# 3_VW_Sensor.net
KiCad netlist of a schematic drawn in Altium Designer
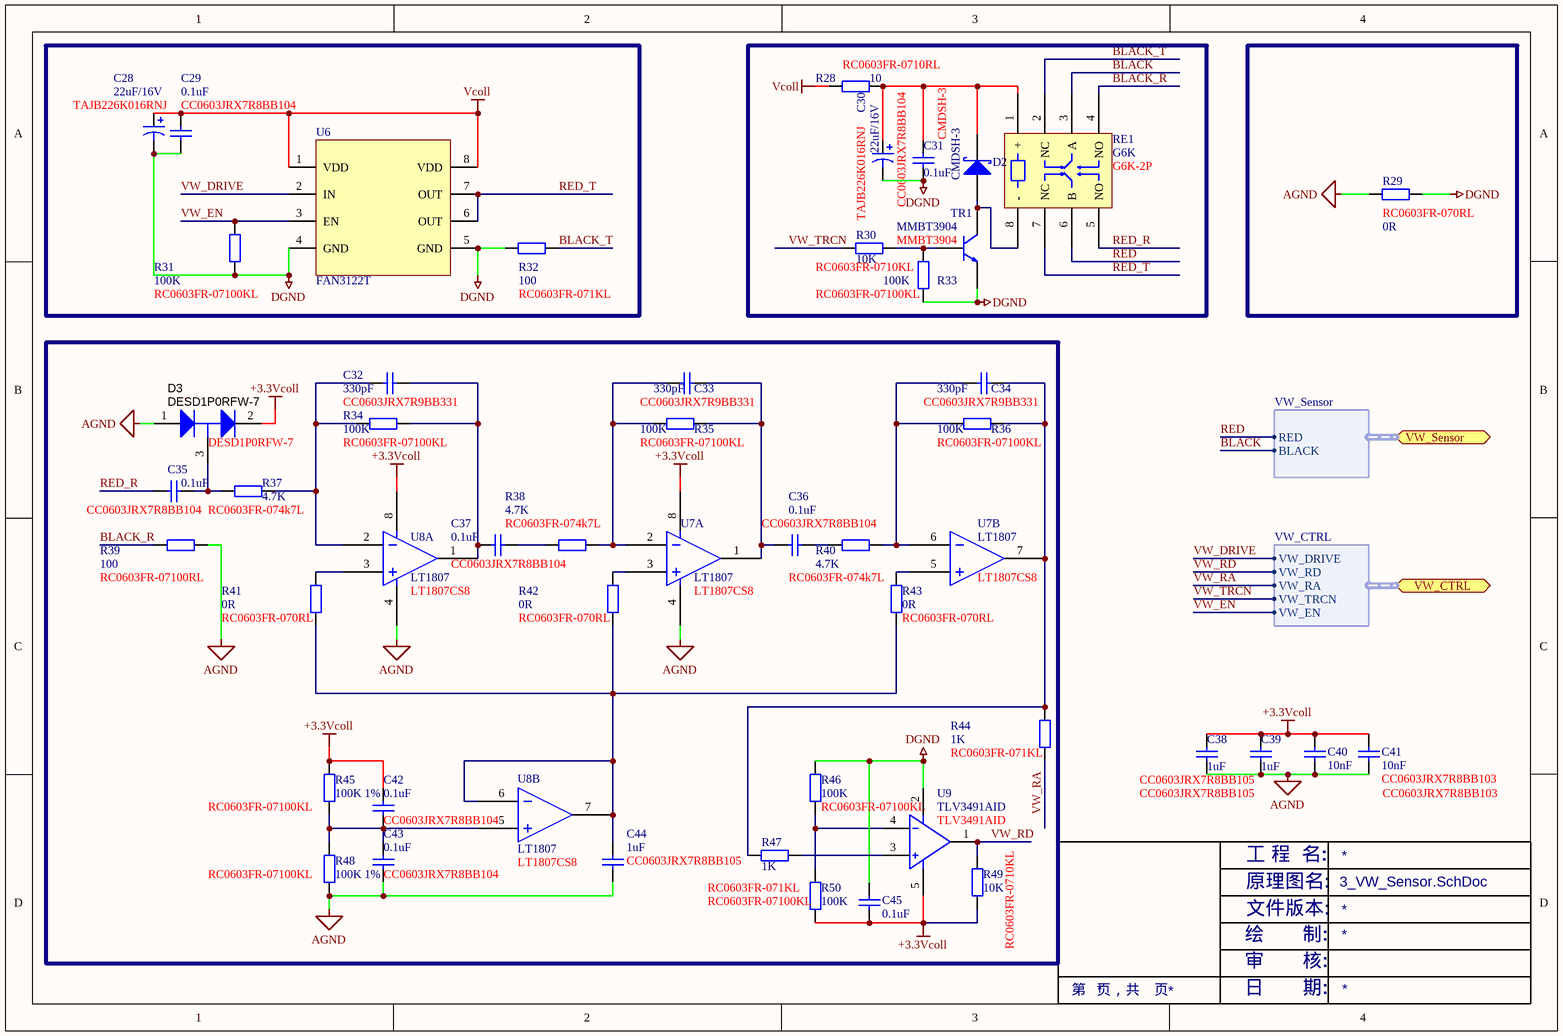
[diagram p0: 3_VW_Sensor.SchDoc]

(export (version "E")
  (design (tool "Eeschema 10.0.6"))
  (components
    (comp (ref "C28")
      (value "22uF/16V")
      (footprint "CB3528")
      (description "Polarized Capacitor (Radial)")
      (fields (field (name "PART NO.") "TAJB226K016RNJ"))
      (libsource (lib "Miscellaneous Devices") (part "Cap Pol1"))
    )
    (comp (ref "C29")
      (value "0.1uF")
      (footprint "CC0603")
      (description "Capacitor")
      (fields (field (name "TYPE NO.") "CC0603JRX7R8BB104"))
      (libsource (lib "Miscellaneous Devices") (part "Cap"))
    )
    (comp (ref "C30")
      (value "22uF/16V")
      (footprint "CB3528")
      (description "Polarized Capacitor (Radial)")
      (fields (field (name "PART NO.") "TAJB226K016RNJ"))
      (libsource (lib "Miscellaneous Devices") (part "Cap Pol1"))
    )
    (comp (ref "C31")
      (value "0.1uF")
      (footprint "CC0603")
      (description "Capacitor")
      (fields (field (name "TYPE NO.") "CC0603JRX7R8BB104"))
      (libsource (lib "Miscellaneous Devices") (part "Cap"))
    )
    (comp (ref "C32")
      (value "330pF")
      (footprint "CC0603")
      (description "Capacitor")
      (fields (field (name "TYPE NO.") "CC0603JRX7R9BB331"))
      (libsource (lib "Miscellaneous Devices") (part "Cap"))
    )
    (comp (ref "C33")
      (value "330pF")
      (footprint "CC0603")
      (description "Capacitor")
      (fields (field (name "TYPE NO.") "CC0603JRX7R9BB331"))
      (libsource (lib "Miscellaneous Devices") (part "Cap"))
    )
    (comp (ref "C34")
      (value "330pF")
      (footprint "CC0603")
      (description "Capacitor")
      (fields (field (name "TYPE NO.") "CC0603JRX7R9BB331"))
      (libsource (lib "Miscellaneous Devices") (part "Cap"))
    )
    (comp (ref "C35")
      (value "0.1uF")
      (footprint "CC0603")
      (description "Capacitor")
      (fields (field (name "TYPE NO.") "CC0603JRX7R8BB104"))
      (libsource (lib "Miscellaneous Devices") (part "Cap"))
    )
    (comp (ref "C36")
      (value "0.1uF")
      (footprint "CC0603")
      (description "Capacitor")
      (fields (field (name "TYPE NO.") "CC0603JRX7R8BB104"))
      (libsource (lib "Miscellaneous Devices") (part "Cap"))
    )
    (comp (ref "C37")
      (value "0.1uF")
      (footprint "CC0603")
      (description "Capacitor")
      (fields (field (name "TYPE NO.") "CC0603JRX7R8BB104"))
      (libsource (lib "Miscellaneous Devices") (part "Cap"))
    )
    (comp (ref "C38")
      (value "1uF")
      (footprint "CC0603")
      (description "Capacitor")
      (fields (field (name "TYPE NO.") "CC0603JRX7R8BB105"))
      (libsource (lib "Miscellaneous Devices") (part "Cap"))
    )
    (comp (ref "C39")
      (value "1uF")
      (footprint "CC0603")
      (description "Capacitor")
      (fields (field (name "TYPE NO.") "CC0603JRX7R8BB105"))
      (libsource (lib "Miscellaneous Devices") (part "Cap"))
    )
    (comp (ref "C40")
      (value "10nF")
      (footprint "CC0603")
      (description "Capacitor")
      (fields (field (name "TYPE NO.") "CC0603JRX7R8BB103"))
      (libsource (lib "Miscellaneous Devices") (part "Cap"))
    )
    (comp (ref "C41")
      (value "10nF")
      (footprint "CC0603")
      (description "Capacitor")
      (fields (field (name "TYPE NO.") "CC0603JRX7R8BB103"))
      (libsource (lib "Miscellaneous Devices") (part "Cap"))
    )
    (comp (ref "C42")
      (value "0.1uF")
      (footprint "CC0603")
      (description "Capacitor")
      (fields (field (name "TYPE NO.") "CC0603JRX7R8BB104"))
      (libsource (lib "Miscellaneous Devices") (part "Cap"))
    )
    (comp (ref "C43")
      (value "0.1uF")
      (footprint "CC0603")
      (description "Capacitor")
      (fields (field (name "TYPE NO.") "CC0603JRX7R8BB104"))
      (libsource (lib "Miscellaneous Devices") (part "Cap"))
    )
    (comp (ref "C44")
      (value "1uF")
      (footprint "CC0603")
      (description "Capacitor")
      (fields (field (name "TYPE NO.") "CC0603JRX7R8BB105"))
      (libsource (lib "Miscellaneous Devices") (part "Cap"))
    )
    (comp (ref "C45")
      (value "0.1uF")
      (footprint "CC0603")
      (description "Capacitor")
      (fields (field (name "PUBLISHER") "Altium Limited"))
      (libsource (lib "Miscellaneous Devices") (part "Cap"))
    )
    (comp (ref "D2")
      (value "CMDSH-3")
      (footprint "SOD323")
      (description "Schottky Diode")
      (fields (field (name "TYPE NO.") "CMDSH-3"))
      (libsource (lib "Miscellaneous Devices") (part "D Schottky"))
    )
    (comp (ref "D3")
      (value "DESD1P0RFW-7")
      (footprint "SOT-323")
      (description "TVS DIODE,70VVVM,8VC,SOT-323")
      (fields (field (name "TYPE NO.") "DESD1P0RFW-7"))
      (libsource (lib "Diode") (part "BAV99WT1G"))
    )
    (comp (ref "R28")
      (value "10")
      (footprint "CC0603")
      (description "Resistor")
      (fields (field (name "TYPE NO.") "RC0603FR-0710RL"))
      (libsource (lib "") (part "Res2_3"))
    )
    (comp (ref "R29")
      (value "0R")
      (footprint "CC0603")
      (description "Resistor")
      (fields (field (name "TYPE NO.") "RC0603FR-070RL"))
      (libsource (lib "") (part "Res2_2"))
    )
    (comp (ref "R30")
      (value "10K")
      (footprint "CC0603")
      (description "Resistor")
      (fields (field (name "TYPE NO.") "RC0603FR-0710KL"))
      (libsource (lib "") (part "Res2_3"))
    )
    (comp (ref "R31")
      (value "100K")
      (footprint "CC0603")
      (description "Resistor")
      (fields (field (name "TYPE NO.") "RC0603FR-07100KL"))
      (libsource (lib "") (part "Res2_1"))
    )
    (comp (ref "R32")
      (value "100")
      (footprint "CC0603")
      (description "Resistor")
      (fields (field (name "TYPE NO.") "RC0603FR-071KL"))
      (libsource (lib "Miscellaneous Devices") (part "Res2"))
    )
    (comp (ref "R33")
      (value "100K")
      (footprint "CC0603")
      (description "Resistor")
      (fields (field (name "TYPE NO.") "RC0603FR-07100KL"))
      (libsource (lib "") (part "Res2_2"))
    )
    (comp (ref "R34")
      (value "100K")
      (footprint "CC0603")
      (description "Resistor")
      (fields (field (name "TYPE NO.") "RC0603FR-07100KL"))
      (libsource (lib "Miscellaneous Devices") (part "Res2"))
    )
    (comp (ref "R35")
      (value "100K")
      (footprint "CC0603")
      (description "Resistor")
      (fields (field (name "TYPE NO.") "RC0603FR-07100KL"))
      (libsource (lib "Miscellaneous Devices") (part "Res2"))
    )
    (comp (ref "R36")
      (value "100K")
      (footprint "CC0603")
      (description "Resistor")
      (fields (field (name "TYPE NO.") "RC0603FR-07100KL"))
      (libsource (lib "Miscellaneous Devices") (part "Res2"))
    )
    (comp (ref "R37")
      (value "4.7K")
      (footprint "CC0603")
      (description "Resistor")
      (fields (field (name "TYPE NO.") "RC0603FR-074k7L"))
      (libsource (lib "Miscellaneous Devices") (part "Res2"))
    )
    (comp (ref "R38")
      (value "4.7K")
      (footprint "CC0603")
      (description "Resistor")
      (fields (field (name "TYPE NO.") "RC0603FR-074k7L"))
      (libsource (lib "Miscellaneous Devices") (part "Res2"))
    )
    (comp (ref "R39")
      (value "100")
      (footprint "CC0603")
      (description "Resistor")
      (fields (field (name "TYPE NO.") "RC0603FR-07100RL"))
      (libsource (lib "") (part "Res2_2"))
    )
    (comp (ref "R40")
      (value "4.7K")
      (footprint "CC0603")
      (description "Resistor")
      (fields (field (name "TYPE NO.") "RC0603FR-074k7L"))
      (libsource (lib "Miscellaneous Devices") (part "Res2"))
    )
    (comp (ref "R41")
      (value "0R")
      (footprint "CC0603")
      (description "Resistor")
      (fields (field (name "TYPE NO.") "RC0603FR-070RL"))
      (libsource (lib "") (part "Res2_1"))
    )
    (comp (ref "R42")
      (value "0R")
      (footprint "CC0603")
      (description "Resistor")
      (fields (field (name "TYPE NO.") "RC0603FR-070RL"))
      (libsource (lib "") (part "Res2_1"))
    )
    (comp (ref "R43")
      (value "0R")
      (footprint "CC0603")
      (description "Resistor")
      (fields (field (name "TYPE NO.") "RC0603FR-070RL"))
      (libsource (lib "") (part "Res2_1"))
    )
    (comp (ref "R44")
      (value "1K")
      (footprint "CC0603")
      (description "Resistor")
      (fields (field (name "TYPE NO.") "RC0603FR-071KL"))
      (libsource (lib "") (part "Res2_1"))
    )
    (comp (ref "R45")
      (value "100K 1%")
      (footprint "CC0603")
      (description "Resistor")
      (fields (field (name "TYPE NO.") "RC0603FR-07100KL"))
      (libsource (lib "") (part "Res2_1"))
    )
    (comp (ref "R46")
      (value "100K")
      (footprint "CC0603")
      (description "Resistor")
      (fields (field (name "TYPE NO.") "RC0603FR-07100KL"))
      (libsource (lib "") (part "Res2_3"))
    )
    (comp (ref "R47")
      (value "1K")
      (footprint "CC0603")
      (description "Resistor")
      (fields (field (name "TYPE NO.") "RC0603FR-071KL"))
      (libsource (lib "Miscellaneous Devices") (part "Res2"))
    )
    (comp (ref "R48")
      (value "100K 1%")
      (footprint "CC0603")
      (description "Resistor")
      (fields (field (name "TYPE NO.") "RC0603FR-07100KL"))
      (libsource (lib "") (part "Res2_1"))
    )
    (comp (ref "R49")
      (value "10K")
      (footprint "CC0603")
      (description "Resistor")
      (fields (field (name "TYPE NO.") "RC0603FR-0710KL"))
      (libsource (lib "") (part "Res2_3"))
    )
    (comp (ref "R50")
      (value "100K")
      (footprint "CC0603")
      (description "Resistor")
      (fields (field (name "TYPE NO.") "RC0603FR-07100KL"))
      (libsource (lib "") (part "Res2_3"))
    )
    (comp (ref "RE1")
      (value "G6K")
      (footprint "G6K")
      (fields (field (name "TYPE NO.") "G6K-2P"))
      (libsource (lib "woylib2015") (part "G6K"))
    )
    (comp (ref "TR1")
      (value "MMBT3904")
      (footprint "SOT-23W")
      (fields (field (name "TYPE NO.") "MMBT3904"))
      (libsource (lib "Discrete") (part "NPN"))
    )
    (comp (ref "U6") (value "FAN3122T") (footprint "SO-8") (libsource (lib "IC") (part "FAN3122")))
    (comp (ref "U7")
      (value "LT1807")
      (footprint "SO-8")
      (fields (field (name "TYPE NO.") "LT1807CS8"))
      (libsource (lib "woylib2015") (part "LM833N"))
    )
    (comp (ref "U8")
      (value "LT1807")
      (footprint "SO-8")
      (fields (field (name "TYPE NO.") "LT1807CS8"))
      (libsource (lib "woylib2015") (part "LM833N"))
    )
    (comp (ref "U9")
      (value "TLV3491AID")
      (footprint "SOT-23-5")
      (fields (field (name "TYPE NO.") "TLV3491AID"))
      (libsource (lib "woylib2015") (part "TLV3491AID"))
    )
  )
  (nets
    (net (code "3") (name "+3.3Vcoll") (class "Default")
      (node (ref "C38") (pin "2") (pinfunction "2_2") (pintype "passive"))
      (node (ref "C39") (pin "2") (pinfunction "2_2") (pintype "passive"))
      (node (ref "C40") (pin "1") (pinfunction "1_1") (pintype "passive"))
      (node (ref "C41") (pin "1") (pinfunction "1_1") (pintype "passive"))
      (node (ref "C42") (pin "1") (pinfunction "1_1") (pintype "passive"))
      (node (ref "C45") (pin "2") (pinfunction "2_2") (pintype "passive"))
      (node (ref "D3") (pin "2") (pinfunction "K_2") (pintype "passive"))
      (node (ref "R45") (pin "1") (pinfunction "1_1") (pintype "passive"))
      (node (ref "R49") (pin "1") (pinfunction "1_1") (pintype "passive"))
      (node (ref "R50") (pin "1") (pinfunction "1_1") (pintype "passive"))
      (node (ref "U7") (pin "8") (pintype "passive"))
      (node (ref "U8") (pin "8") (pintype "passive"))
      (node (ref "U9") (pin "5") (pinfunction "+VS_5") (pintype "passive"))
    )
    (net (code "4") (name "/BLACK") (class "Default")
      (node (ref "RE1") (pin "3") (pinfunction "A_3") (pintype "passive"))
    )
    (net (code "5") (name "/BLACK_R") (class "Default")
      (node (ref "R39") (pin "1") (pinfunction "1_1") (pintype "passive"))
      (node (ref "RE1") (pin "4") (pinfunction "NO_4") (pintype "passive"))
    )
    (net (code "6") (name "/BLACK_T") (class "Default")
      (node (ref "R32") (pin "1") (pinfunction "1_1") (pintype "passive"))
      (node (ref "RE1") (pin "2") (pinfunction "NC_2") (pintype "passive"))
    )
    (net (code "7") (name "/RED") (class "Default")
      (node (ref "RE1") (pin "6") (pinfunction "B_6") (pintype "passive"))
    )
    (net (code "8") (name "/RED_R") (class "Default")
      (node (ref "C35") (pin "2") (pinfunction "2_2") (pintype "passive"))
      (node (ref "RE1") (pin "5") (pinfunction "NO_5") (pintype "passive"))
    )
    (net (code "9") (name "/RED_T") (class "Default")
      (node (ref "RE1") (pin "7") (pinfunction "NC_7") (pintype "passive"))
      (node (ref "U6") (pin "6") (pinfunction "OUT_6") (pintype "passive"))
      (node (ref "U6") (pin "7") (pinfunction "OUT_7") (pintype "passive"))
    )
    (net (code "10") (name "/VW_DRIVE") (class "Default")
      (node (ref "U6") (pin "2") (pinfunction "IN_2") (pintype "passive"))
    )
    (net (code "11") (name "/VW_EN") (class "Default")
      (node (ref "R31") (pin "1") (pinfunction "1_1") (pintype "passive"))
      (node (ref "U6") (pin "3") (pinfunction "EN_3") (pintype "passive"))
    )
    (net (code "12") (name "/VW_RA") (class "Default")
      (node (ref "R44") (pin "2") (pinfunction "2_2") (pintype "passive"))
    )
    (net (code "13") (name "/VW_RD") (class "Default")
      (node (ref "R49") (pin "2") (pinfunction "2_2") (pintype "passive"))
      (node (ref "U9") (pin "1") (pinfunction "OUT_1") (pintype "passive"))
    )
    (net (code "14") (name "/VW_TRCN") (class "Default")
      (node (ref "R30") (pin "1") (pinfunction "1_1") (pintype "passive"))
    )
    (net (code "17") (name "AGND") (class "Default")
      (node (ref "C38") (pin "1") (pinfunction "1_1") (pintype "passive"))
      (node (ref "C39") (pin "1") (pinfunction "1_1") (pintype "passive"))
      (node (ref "C40") (pin "2") (pinfunction "2_2") (pintype "passive"))
      (node (ref "C41") (pin "2") (pinfunction "2_2") (pintype "passive"))
      (node (ref "C43") (pin "2") (pinfunction "2_2") (pintype "passive"))
      (node (ref "C44") (pin "1") (pinfunction "1_1") (pintype "passive"))
      (node (ref "D3") (pin "1") (pinfunction "A_1") (pintype "passive"))
      (node (ref "R29") (pin "1") (pinfunction "1_1") (pintype "passive"))
      (node (ref "R39") (pin "2") (pinfunction "2_2") (pintype "passive"))
      (node (ref "R48") (pin "2") (pinfunction "2_2") (pintype "passive"))
      (node (ref "U7") (pin "4") (pintype "passive"))
      (node (ref "U8") (pin "4") (pintype "passive"))
    )
    (net (code "18") (name "DGND") (class "Default")
      (node (ref "C28") (pin "2") (pinfunction "2_2") (pintype "passive"))
      (node (ref "C29") (pin "1") (pinfunction "1_1") (pintype "passive"))
      (node (ref "C30") (pin "2") (pinfunction "2_2") (pintype "passive"))
      (node (ref "C31") (pin "2") (pinfunction "2_2") (pintype "passive"))
      (node (ref "C45") (pin "1") (pinfunction "1_1") (pintype "passive"))
      (node (ref "R29") (pin "2") (pinfunction "2_2") (pintype "passive"))
      (node (ref "R31") (pin "2") (pinfunction "2_2") (pintype "passive"))
      (node (ref "R32") (pin "2") (pinfunction "2_2") (pintype "passive"))
      (node (ref "R33") (pin "1") (pinfunction "1_1") (pintype "passive"))
      (node (ref "R46") (pin "2") (pinfunction "2_2") (pintype "passive"))
      (node (ref "TR1") (pin "2") (pinfunction "2_2") (pintype "passive"))
      (node (ref "U6") (pin "4") (pinfunction "GND_4") (pintype "passive"))
      (node (ref "U6") (pin "5") (pinfunction "GND_5") (pintype "passive"))
      (node (ref "U9") (pin "2") (pinfunction "-VS_2") (pintype "passive"))
    )
    (net (code "19") (name "Net-(C32-Pad1)") (class "Default")
      (node (ref "C32") (pin "1") (pinfunction "1_1") (pintype "passive"))
      (node (ref "C37") (pin "2") (pinfunction "2_2") (pintype "passive"))
      (node (ref "R34") (pin "1") (pinfunction "1_1") (pintype "passive"))
      (node (ref "U8") (pin "1") (pintype "passive"))
    )
    (net (code "20") (name "Net-(C32-Pad2)") (class "Default")
      (node (ref "C32") (pin "2") (pinfunction "2_2") (pintype "passive"))
      (node (ref "R34") (pin "2") (pinfunction "2_2") (pintype "passive"))
      (node (ref "R37") (pin "1") (pinfunction "1_1") (pintype "passive"))
      (node (ref "U8") (pin "2") (pintype "passive"))
    )
    (net (code "21") (name "Net-(C33-Pad1)") (class "Default")
      (node (ref "C33") (pin "1") (pinfunction "1_1") (pintype "passive"))
      (node (ref "C36") (pin "2") (pinfunction "2_2") (pintype "passive"))
      (node (ref "R35") (pin "1") (pinfunction "1_1") (pintype "passive"))
      (node (ref "U7") (pin "1") (pintype "passive"))
    )
    (net (code "22") (name "Net-(C33-Pad2)") (class "Default")
      (node (ref "C33") (pin "2") (pinfunction "2_2") (pintype "passive"))
      (node (ref "R35") (pin "2") (pinfunction "2_2") (pintype "passive"))
      (node (ref "R38") (pin "1") (pinfunction "1_1") (pintype "passive"))
      (node (ref "U7") (pin "2") (pintype "passive"))
    )
    (net (code "23") (name "Net-(C34-Pad1)") (class "Default")
      (node (ref "C34") (pin "1") (pinfunction "1_1") (pintype "passive"))
      (node (ref "R36") (pin "1") (pinfunction "1_1") (pintype "passive"))
      (node (ref "R44") (pin "1") (pinfunction "1_1") (pintype "passive"))
      (node (ref "R47") (pin "2") (pinfunction "2_2") (pintype "passive"))
      (node (ref "U7") (pin "7") (pintype "passive"))
    )
    (net (code "24") (name "Net-(C34-Pad2)") (class "Default")
      (node (ref "C34") (pin "2") (pinfunction "2_2") (pintype "passive"))
      (node (ref "R36") (pin "2") (pinfunction "2_2") (pintype "passive"))
      (node (ref "R40") (pin "1") (pinfunction "1_1") (pintype "passive"))
      (node (ref "U7") (pin "6") (pintype "passive"))
    )
    (net (code "25") (name "Net-(C36-Pad1)") (class "Default")
      (node (ref "C36") (pin "1") (pinfunction "1_1") (pintype "passive"))
      (node (ref "R40") (pin "2") (pinfunction "2_2") (pintype "passive"))
    )
    (net (code "26") (name "Net-(C37-Pad1)") (class "Default")
      (node (ref "C37") (pin "1") (pinfunction "1_1") (pintype "passive"))
      (node (ref "R38") (pin "2") (pinfunction "2_2") (pintype "passive"))
    )
    (net (code "27") (name "Net-(C42-Pad2)") (class "Default")
      (node (ref "C42") (pin "2") (pinfunction "2_2") (pintype "passive"))
      (node (ref "C43") (pin "1") (pinfunction "1_1") (pintype "passive"))
      (node (ref "R45") (pin "2") (pinfunction "2_2") (pintype "passive"))
      (node (ref "R48") (pin "1") (pinfunction "1_1") (pintype "passive"))
      (node (ref "U8") (pin "5") (pintype "passive"))
    )
    (net (code "28") (name "Net-(C44-Pad2)") (class "Default")
      (node (ref "C44") (pin "2") (pinfunction "2_2") (pintype "passive"))
      (node (ref "R41") (pin "2") (pinfunction "2_2") (pintype "passive"))
      (node (ref "R42") (pin "2") (pinfunction "2_2") (pintype "passive"))
      (node (ref "R43") (pin "2") (pinfunction "2_2") (pintype "passive"))
      (node (ref "U8") (pin "6") (pintype "passive"))
      (node (ref "U8") (pin "7") (pintype "passive"))
    )
    (net (code "29") (name "Net-(D2-A)") (class "Default")
      (node (ref "D2") (pin "1") (pinfunction "A_1") (pintype "passive"))
      (node (ref "RE1") (pin "8") (pinfunction "-_8") (pintype "passive"))
      (node (ref "TR1") (pin "3") (pinfunction "3_3") (pintype "passive"))
    )
    (net (code "30") (name "Net-(D2-K)") (class "Default")
      (node (ref "C30") (pin "1") (pinfunction "1_1") (pintype "passive"))
      (node (ref "C31") (pin "1") (pinfunction "1_1") (pintype "passive"))
      (node (ref "D2") (pin "2") (pinfunction "K_2") (pintype "passive"))
      (node (ref "R28") (pin "2") (pinfunction "2_2") (pintype "passive"))
      (node (ref "RE1") (pin "1") (pinfunction "+_1") (pintype "passive"))
    )
    (net (code "31") (name "Net-(D3-C)") (class "Default")
      (node (ref "C35") (pin "1") (pinfunction "1_1") (pintype "passive"))
      (node (ref "D3") (pin "3") (pinfunction "C_3") (pintype "passive"))
      (node (ref "R37") (pin "2") (pinfunction "2_2") (pintype "passive"))
    )
    (net (code "32") (name "Net-(R30-Pad2)") (class "Default")
      (node (ref "R30") (pin "2") (pinfunction "2_2") (pintype "passive"))
      (node (ref "R33") (pin "2") (pinfunction "2_2") (pintype "passive"))
      (node (ref "TR1") (pin "1") (pinfunction "1_1") (pintype "passive"))
    )
    (net (code "33") (name "Net-(R41-Pad1)") (class "Default")
      (node (ref "R41") (pin "1") (pinfunction "1_1") (pintype "passive"))
      (node (ref "U8") (pin "3") (pintype "passive"))
    )
    (net (code "34") (name "Net-(R42-Pad1)") (class "Default")
      (node (ref "R42") (pin "1") (pinfunction "1_1") (pintype "passive"))
      (node (ref "U7") (pin "3") (pintype "passive"))
    )
    (net (code "35") (name "Net-(R43-Pad1)") (class "Default")
      (node (ref "R43") (pin "1") (pinfunction "1_1") (pintype "passive"))
      (node (ref "U7") (pin "5") (pintype "passive"))
    )
    (net (code "36") (name "Net-(U9-+)") (class "Default")
      (node (ref "R47") (pin "1") (pinfunction "1_1") (pintype "passive"))
      (node (ref "U9") (pin "3") (pinfunction "+_3") (pintype "passive"))
    )
    (net (code "37") (name "Net-(U9--)") (class "Default")
      (node (ref "R46") (pin "1") (pinfunction "1_1") (pintype "passive"))
      (node (ref "R50") (pin "2") (pinfunction "2_2") (pintype "passive"))
      (node (ref "U9") (pin "4") (pinfunction "-_4") (pintype "passive"))
    )
    (net (code "38") (name "Vcoll") (class "Default")
      (node (ref "C28") (pin "1") (pinfunction "1_1") (pintype "passive"))
      (node (ref "C29") (pin "2") (pinfunction "2_2") (pintype "passive"))
      (node (ref "R28") (pin "1") (pinfunction "1_1") (pintype "passive"))
      (node (ref "U6") (pin "1") (pinfunction "VDD_1") (pintype "passive"))
      (node (ref "U6") (pin "8") (pinfunction "VDD_8") (pintype "passive"))
    )
  )
)
